# File_Nguyen_Ly.net
KiCad netlist of a schematic drawn in Altium Designer
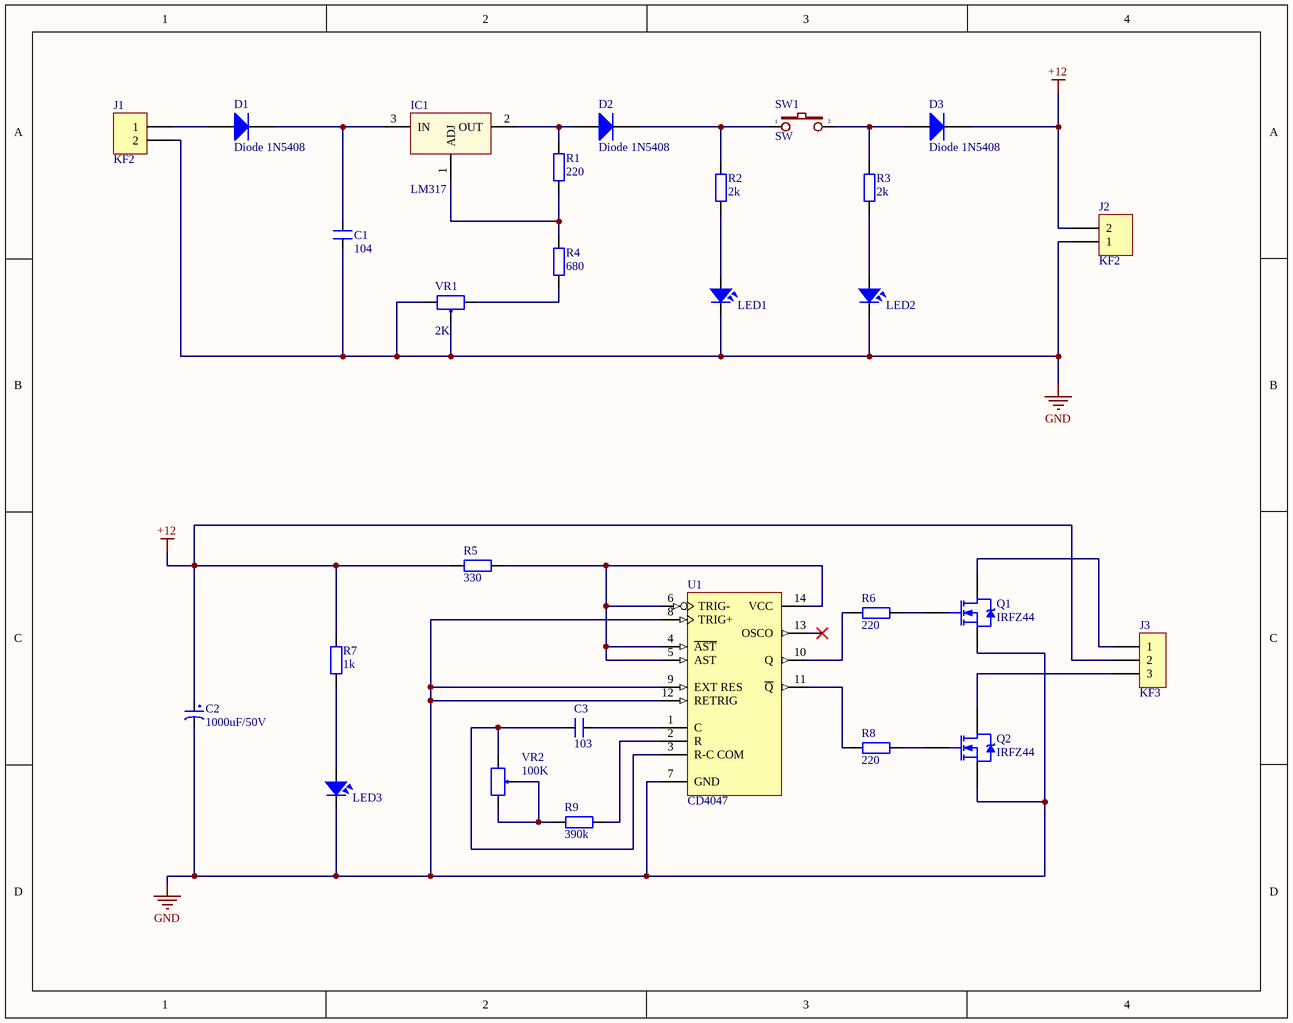
[diagram p0: File_Nguyen_Ly.SchDoc]

(export (version "E")
  (design (tool "Eeschema 10.0.6"))
  (components
    (comp (ref "C1")
      (value "104")
      (footprint "CN2")
      (description "Cap np 104 => 105pF")
      (libsource (lib "hphonglib") (part "CN2"))
    )
    (comp (ref "C2")
      (value "1000uF/50V")
      (footprint "CP3/7")
      (description "Cap 4700uF/16V - 2200uF/50V")
      (libsource (lib "syhaunguyen") (part "CP6"))
    )
    (comp (ref "C3")
      (value "103")
      (footprint "CN1.5")
      (description "Cap np 682pF => 104pF")
      (libsource (lib "syhaunguyen") (part "CN1.5"))
    )
    (comp (ref "D1")
      (value "Diode 1N5408")
      (footprint "DO-201AD")
      (description "3 Amp Medium Power Silicon Rectifier Diode")
      (fields (field (name "PUBLISHER") "Altium Limited"))
      (libsource (lib "Miscellaneous Devices") (part "Diode 1N5408"))
    )
    (comp (ref "D2")
      (value "Diode 1N5408")
      (footprint "DO-201AD")
      (description "3 Amp Medium Power Silicon Rectifier Diode")
      (fields (field (name "PUBLISHER") "Altium Limited"))
      (libsource (lib "Miscellaneous Devices") (part "Diode 1N5408"))
    )
    (comp (ref "D3")
      (value "Diode 1N5408")
      (footprint "DO-201AD")
      (description "3 Amp Medium Power Silicon Rectifier Diode")
      (fields (field (name "PUBLISHER") "Altium Limited"))
      (libsource (lib "Miscellaneous Devices") (part "Diode 1N5408"))
    )
    (comp (ref "IC1")
      (value "LM317")
      (footprint "TO220H1")
      (description "Adj Voltage +1.2 -> +37V")
      (libsource (lib "LIBRARY1") (part "LM317"))
    )
    (comp (ref "J1")
      (value "KF2")
      (footprint "KF2-5.08")
      (fields
        (field (name "MANUFACTURER") "Würth Elektronik eiSos GmbH")
        (field (name "PARTNO") "691103110002")
        (field (name "CREATED BY") "Karrer Zheng")
      )
      (libsource (lib "LIBRARY1") (part "KF2"))
    )
    (comp (ref "J2")
      (value "KF2")
      (footprint "KF2-7.62")
      (fields
        (field (name "MANUFACTURER") "Würth Elektronik eiSos GmbH")
        (field (name "PARTNO") "691103110002")
        (field (name "CREATED BY") "Karrer Zheng")
      )
      (libsource (lib "TechMT.VN_Lib_Project v2") (part "KF2"))
    )
    (comp (ref "J3")
      (value "KF3")
      (footprint "KF3-7.62")
      (fields
        (field (name "MANUFACTURER") "Würth Elektronik eiSos GmbH")
        (field (name "PARTNO") "691103110003")
        (field (name "CREATED BY") "Karrer Zheng")
      )
      (libsource (lib "TechMT.VN_Lib_Project v2") (part "KF3"))
    )
    (comp (ref "LED1")
      (value "LED")
      (footprint "LED-5-Green")
      (description "LED Single colour Green and Red")
      (libsource (lib "syhaunguyen") (part "LED"))
    )
    (comp (ref "LED2")
      (value "LED")
      (footprint "LED-5-RED")
      (description "LED Single colour Green and Red")
      (libsource (lib "syhaunguyen") (part "LED"))
    )
    (comp (ref "LED3")
      (value "LED")
      (footprint "LED-5-BLUE")
      (description "LED Single colour Green and Red")
      (libsource (lib "syhaunguyen") (part "LED"))
    )
    (comp (ref "Q1") (value "IRFZ44") (footprint "TO220H2") (libsource (lib "LIBRARY1") (part "IRFZ44")))
    (comp (ref "Q2") (value "IRFZ44") (footprint "TO220H2") (libsource (lib "LIBRARY1") (part "IRFZ44")))
    (comp (ref "R1")
      (value "220")
      (footprint "R1/4W")
      (description "Resistor 1/4W")
      (libsource (lib "syhaunguyen") (part "R1/4W"))
    )
    (comp (ref "R2")
      (value "2k")
      (footprint "R1/4W")
      (description "Resistor 1/4W")
      (libsource (lib "syhaunguyen") (part "R1/4W"))
    )
    (comp (ref "R3")
      (value "2k")
      (footprint "R1/4W")
      (description "Resistor 1/4W")
      (libsource (lib "syhaunguyen") (part "R1/4W"))
    )
    (comp (ref "R4")
      (value "680")
      (footprint "R1/4W")
      (description "Resistor 1/4W")
      (libsource (lib "syhaunguyen") (part "R1/4W"))
    )
    (comp (ref "R5")
      (value "330")
      (footprint "R1/4W")
      (description "Resistor 1/4W")
      (libsource (lib "syhaunguyen") (part "R1/4W"))
    )
    (comp (ref "R6")
      (value "220")
      (footprint "R1/2W")
      (description "Resistor 1/4W")
      (libsource (lib "syhaunguyen") (part "R1/4W"))
    )
    (comp (ref "R7")
      (value "1k")
      (footprint "R1/4W")
      (description "Resistor 1/4W")
      (libsource (lib "syhaunguyen") (part "R1/4W"))
    )
    (comp (ref "R8")
      (value "220")
      (footprint "R1/2W")
      (description "Resistor 1/4W")
      (libsource (lib "syhaunguyen") (part "R1/4W"))
    )
    (comp (ref "R9")
      (value "390k")
      (footprint "R1/4W")
      (description "Resistor 1/4W")
      (libsource (lib "syhaunguyen") (part "R1/4W"))
    )
    (comp (ref "SW1")
      (value "SW")
      (footprint "SW-DIP1-1")
      (description "Switch button 2 pin")
      (libsource (lib "LIBRARY") (part "SW2"))
    )
    (comp (ref "U1")
      (value "CD4047")
      (footprint "DIP14/W0.3")
      (libsource (lib "syhaunguyen") (part "CD4047"))
    )
    (comp (ref "VR1")
      (value "2K")
      (footprint "VR")
      (description "Var Resistor")
      (libsource (lib "syhaunguyen") (part "VR"))
    )
    (comp (ref "VR2")
      (value "100K")
      (footprint "VR")
      (description "Var Resistor")
      (libsource (lib "syhaunguyen") (part "VR"))
    )
  )
  (nets
    (net (code "1") (name "+12") (class "Default")
      (node (ref "C2") (pin "1") (pinfunction "1_1") (pintype "passive"))
      (node (ref "D3") (pin "2") (pinfunction "K_2") (pintype "passive"))
      (node (ref "J2") (pin "2") (pinfunction "2_2") (pintype "passive"))
      (node (ref "J3") (pin "2") (pinfunction "2_2") (pintype "passive"))
      (node (ref "R5") (pin "2") (pinfunction "2_2") (pintype "passive"))
      (node (ref "R7") (pin "2") (pinfunction "2_2") (pintype "passive"))
    )
    (net (code "2") (name "GND") (class "Default")
      (node (ref "C1") (pin "1") (pinfunction "1_1") (pintype "passive"))
      (node (ref "C2") (pin "2") (pinfunction "2_2") (pintype "passive"))
      (node (ref "J1") (pin "2") (pinfunction "2_2") (pintype "passive"))
      (node (ref "J2") (pin "1") (pinfunction "1_1") (pintype "passive"))
      (node (ref "LED1") (pin "2") (pinfunction "2_2") (pintype "passive"))
      (node (ref "LED2") (pin "2") (pinfunction "2_2") (pintype "passive"))
      (node (ref "LED3") (pin "2") (pinfunction "2_2") (pintype "passive"))
      (node (ref "Q1") (pin "3") (pinfunction "S_3") (pintype "passive"))
      (node (ref "Q2") (pin "3") (pinfunction "S_3") (pintype "passive"))
      (node (ref "U1") (pin "12") (pinfunction "RETRIG_12") (pintype "input"))
      (node (ref "U1") (pin "7") (pinfunction "GND_7") (pintype "power_in"))
      (node (ref "U1") (pin "8") (pinfunction "TRIG+_8") (pintype "input"))
      (node (ref "U1") (pin "9") (pinfunction "EXT_RES_9") (pintype "input"))
      (node (ref "VR1") (pin "2") (pinfunction "2_2") (pintype "passive"))
      (node (ref "VR1") (pin "3") (pinfunction "3_3") (pintype "passive"))
    )
    (net (code "3") (name "Net-(D1-A)") (class "Default")
      (node (ref "D1") (pin "1") (pinfunction "A_1") (pintype "passive"))
      (node (ref "J1") (pin "1") (pinfunction "1_1") (pintype "passive"))
    )
    (net (code "4") (name "Net-(D1-K)") (class "Default")
      (node (ref "C1") (pin "2") (pinfunction "2_2") (pintype "passive"))
      (node (ref "D1") (pin "2") (pinfunction "K_2") (pintype "passive"))
      (node (ref "IC1") (pin "3") (pinfunction "IN_3") (pintype "passive"))
    )
    (net (code "5") (name "Net-(D2-A)") (class "Default")
      (node (ref "D2") (pin "1") (pinfunction "A_1") (pintype "passive"))
      (node (ref "IC1") (pin "2") (pinfunction "OUT_2") (pintype "passive"))
      (node (ref "R1") (pin "2") (pinfunction "2_2") (pintype "passive"))
    )
    (net (code "6") (name "Net-(D2-K)") (class "Default")
      (node (ref "D2") (pin "2") (pinfunction "K_2") (pintype "passive"))
      (node (ref "R2") (pin "1") (pinfunction "1_1") (pintype "passive"))
      (node (ref "SW1") (pin "1") (pinfunction "1_1") (pintype "passive"))
    )
    (net (code "7") (name "Net-(D3-A)") (class "Default")
      (node (ref "D3") (pin "1") (pinfunction "A_1") (pintype "passive"))
      (node (ref "R3") (pin "1") (pinfunction "1_1") (pintype "passive"))
      (node (ref "SW1") (pin "2") (pinfunction "2_2") (pintype "passive"))
    )
    (net (code "8") (name "Net-(IC1-ADJ)") (class "Default")
      (node (ref "IC1") (pin "1") (pinfunction "ADJ_1") (pintype "passive"))
      (node (ref "R1") (pin "1") (pinfunction "1_1") (pintype "passive"))
      (node (ref "R4") (pin "2") (pinfunction "2_2") (pintype "passive"))
    )
    (net (code "9") (name "Net-(LED1-Pad1)") (class "Default")
      (node (ref "LED1") (pin "1") (pinfunction "1_1") (pintype "passive"))
      (node (ref "R2") (pin "2") (pinfunction "2_2") (pintype "passive"))
    )
    (net (code "10") (name "Net-(LED2-Pad1)") (class "Default")
      (node (ref "LED2") (pin "1") (pinfunction "1_1") (pintype "passive"))
      (node (ref "R3") (pin "2") (pinfunction "2_2") (pintype "passive"))
    )
    (net (code "11") (name "Net-(LED3-Pad1)") (class "Default")
      (node (ref "LED3") (pin "1") (pinfunction "1_1") (pintype "passive"))
      (node (ref "R7") (pin "1") (pinfunction "1_1") (pintype "passive"))
    )
    (net (code "12") (name "Net-(Q1-D)") (class "Default")
      (node (ref "J3") (pin "1") (pinfunction "1_1") (pintype "passive"))
      (node (ref "Q1") (pin "2") (pinfunction "D_2") (pintype "passive"))
    )
    (net (code "13") (name "Net-(Q1-G)") (class "Default")
      (node (ref "Q1") (pin "1") (pinfunction "G_1") (pintype "passive"))
      (node (ref "R6") (pin "1") (pinfunction "1_1") (pintype "passive"))
    )
    (net (code "14") (name "Net-(Q2-D)") (class "Default")
      (node (ref "J3") (pin "3") (pinfunction "3_3") (pintype "passive"))
      (node (ref "Q2") (pin "2") (pinfunction "D_2") (pintype "passive"))
    )
    (net (code "15") (name "Net-(Q2-G)") (class "Default")
      (node (ref "Q2") (pin "1") (pinfunction "G_1") (pintype "passive"))
      (node (ref "R8") (pin "1") (pinfunction "1_1") (pintype "passive"))
    )
    (net (code "16") (name "Net-(R4-Pad1)") (class "Default")
      (node (ref "R4") (pin "1") (pinfunction "1_1") (pintype "passive"))
      (node (ref "VR1") (pin "1") (pinfunction "1_1") (pintype "passive"))
    )
    (net (code "17") (name "Net-(R9-Pad2)") (class "Default")
      (node (ref "R9") (pin "2") (pinfunction "2_2") (pintype "passive"))
      (node (ref "VR2") (pin "2") (pinfunction "2_2") (pintype "passive"))
      (node (ref "VR2") (pin "3") (pinfunction "3_3") (pintype "passive"))
    )
    (net (code "18") (name "Net-(U1-AST)") (class "Default")
      (node (ref "R5") (pin "1") (pinfunction "1_1") (pintype "passive"))
      (node (ref "U1") (pin "14") (pinfunction "VCC_14") (pintype "power_in"))
      (node (ref "U1") (pin "4") (pinfunction "~{AST}_4") (pintype "input"))
      (node (ref "U1") (pin "5") (pinfunction "AST_5") (pintype "input"))
      (node (ref "U1") (pin "6") (pinfunction "TRIG-_6") (pintype "input"))
    )
    (net (code "19") (name "Net-(U1-C)") (class "Default")
      (node (ref "C3") (pin "2") (pinfunction "2_2") (pintype "passive"))
      (node (ref "U1") (pin "1") (pinfunction "C_1") (pintype "passive"))
    )
    (net (code "20") (name "Net-(U1-Q)") (class "Default")
      (node (ref "R6") (pin "2") (pinfunction "2_2") (pintype "passive"))
      (node (ref "U1") (pin "10") (pinfunction "Q_10") (pintype "output"))
    )
    (net (code "21") (name "Net-(U1-R)") (class "Default")
      (node (ref "R9") (pin "1") (pinfunction "1_1") (pintype "passive"))
      (node (ref "U1") (pin "2") (pinfunction "R_2") (pintype "passive"))
    )
    (net (code "22") (name "Net-(U1-R-C_COM)") (class "Default")
      (node (ref "C3") (pin "1") (pinfunction "1_1") (pintype "passive"))
      (node (ref "U1") (pin "3") (pinfunction "R-C_COM_3") (pintype "passive"))
      (node (ref "VR2") (pin "1") (pinfunction "1_1") (pintype "passive"))
    )
    (net (code "23") (name "Net-(U1-~{Q})") (class "Default")
      (node (ref "R8") (pin "2") (pinfunction "2_2") (pintype "passive"))
      (node (ref "U1") (pin "11") (pinfunction "~{Q}_11") (pintype "output"))
    )
    (net (code "24") (name "unconnected-(U1-OSCO-Pad13)") (class "Default")
      (node (ref "U1") (pin "13") (pinfunction "OSCO_13") (pintype "output+no_connect"))
    )
  )
)
